# SCH_Potentiometer_Led_MCP3008_2025-04-22.net
KiCad netlist of a schematic drawn in EasyEDA
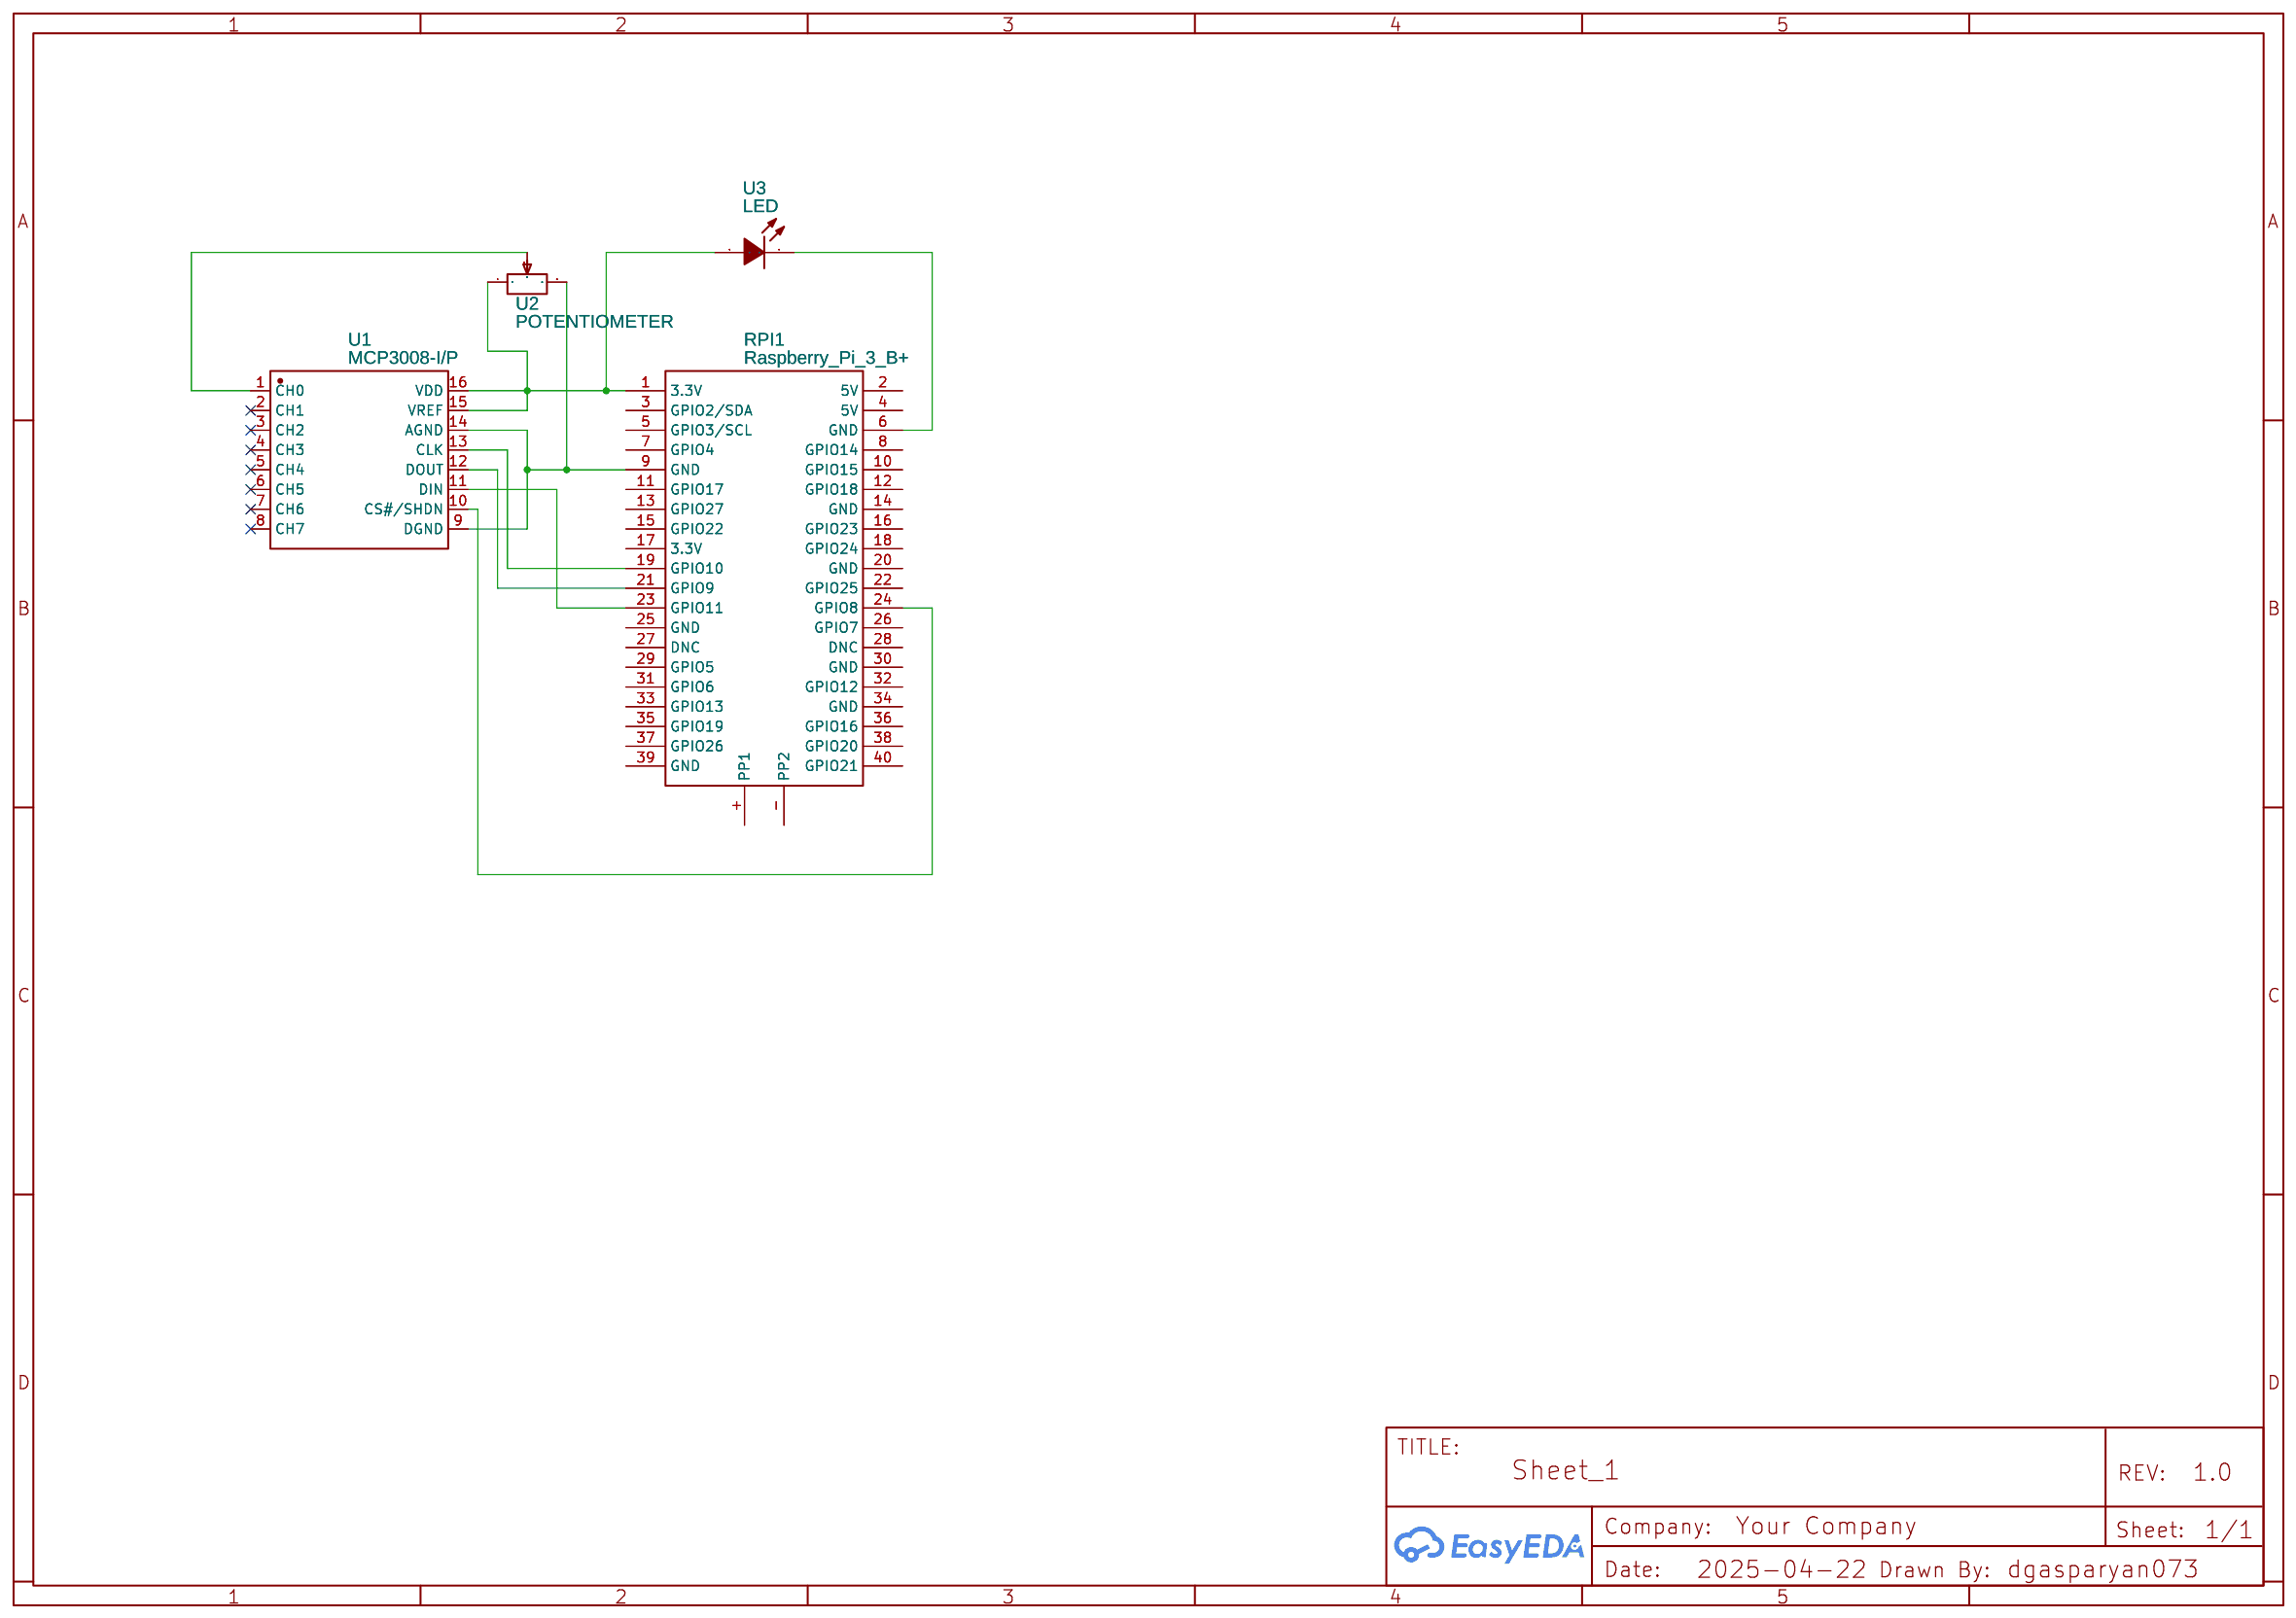
[diagram p0: schematic sheet]

(export (version "E")
  (design (tool "Eeschema 10.0.6"))
  (components
    (comp (ref "RPI1")
      (value "Raspberry_Pi_3_B+")
      (fields
        (field (name "Manufacturer Part") "Raspberry Pi 3 - Model B+ - 1.4GHz Cortex-A53 with 1GB RAM")
        (field (name "Manufacturer") "Raspberry Pi")
      )
      (libsource (lib "") (part "Raspberry_Pi_3_B+"))
    )
    (comp (ref "U1")
      (value "MCP3008-I/P")
      (fields (field (name "Manufacturer") "MICROCHIP(美国微芯)"))
      (libsource (lib "") (part "MCP3008-I/P"))
    )
    (comp (ref "U2")
      (value "POTENTIOMETER")
      (fields (field (name "Manufacturer Part") "3*3Potentiometer-10kΩ20%"))
      (libsource (lib "") (part "3*3POTENTIOMETER-10KΩ20%"))
    )
    (comp (ref "U3")
      (value "LED")
      (fields (field (name "Manufacturer Part") "720-LCGH9RNMXNX1"))
      (libsource (lib "") (part "720-LCGH9RNMXNX1"))
    )
  )
  (nets
    (net (code "1") (name "Net-(RPI1-GPIO8)") (class "Default")
      (node (ref "RPI1") (pin "24") (pinfunction "GPIO8_24") (pintype "bidirectional"))
      (node (ref "U1") (pin "10") (pinfunction "CS#/SHDN_10") (pintype "unspecified"))
    )
    (net (code "2") (name "Net-(RPI1-GPIO9)") (class "Default")
      (node (ref "RPI1") (pin "21") (pinfunction "GPIO9_21") (pintype "bidirectional"))
      (node (ref "U1") (pin "12") (pinfunction "DOUT_12") (pintype "unspecified"))
    )
    (net (code "3") (name "Net-(RPI1-GPIO10)") (class "Default")
      (node (ref "RPI1") (pin "19") (pinfunction "GPIO10_19") (pintype "bidirectional"))
      (node (ref "U1") (pin "13") (pinfunction "CLK_13") (pintype "unspecified"))
    )
    (net (code "4") (name "Net-(RPI1-GPIO11)") (class "Default")
      (node (ref "RPI1") (pin "23") (pinfunction "GPIO11_23") (pintype "bidirectional"))
      (node (ref "U1") (pin "11") (pinfunction "DIN_11") (pintype "unspecified"))
    )
    (net (code "5") (name "Net-(U1-AGND)") (class "Default")
      (node (ref "RPI1") (pin "9") (pinfunction "GND_9") (pintype "unspecified"))
      (node (ref "U1") (pin "14") (pinfunction "AGND_14") (pintype "unspecified"))
      (node (ref "U1") (pin "9") (pinfunction "DGND_9") (pintype "unspecified"))
      (node (ref "U2") (pin "3") (pinfunction "3_3") (pintype "input"))
    )
    (net (code "6") (name "Net-(U1-CH0)") (class "Default")
      (node (ref "U1") (pin "1") (pinfunction "CH0_1") (pintype "unspecified"))
      (node (ref "U2") (pin "2") (pinfunction "2_2") (pintype "input"))
    )
    (net (code "7") (name "Net-(U1-VDD)") (class "Default")
      (node (ref "RPI1") (pin "1") (pinfunction "3.3V_1") (pintype "passive"))
      (node (ref "U1") (pin "15") (pinfunction "VREF_15") (pintype "unspecified"))
      (node (ref "U1") (pin "16") (pinfunction "VDD_16") (pintype "unspecified"))
      (node (ref "U2") (pin "1") (pinfunction "1_1") (pintype "input"))
      (node (ref "U3") (pin "2") (pinfunction "A_2") (pintype "unspecified"))
    )
    (net (code "8") (name "Net-(U3-K)") (class "Default")
      (node (ref "RPI1") (pin "6") (pinfunction "GND_6") (pintype "unspecified"))
      (node (ref "U3") (pin "1") (pinfunction "K_1") (pintype "unspecified"))
    )
    (net (code "9") (name "unconnected-(RPI1-3.3V-Pad17)") (class "Default")
      (node (ref "RPI1") (pin "17") (pinfunction "3.3V_17") (pintype "passive"))
    )
    (net (code "10") (name "unconnected-(RPI1-5V-Pad2)") (class "Default")
      (node (ref "RPI1") (pin "2") (pinfunction "5V_2") (pintype "passive"))
    )
    (net (code "11") (name "unconnected-(RPI1-5V-Pad4)") (class "Default")
      (node (ref "RPI1") (pin "4") (pinfunction "5V_4") (pintype "passive"))
    )
    (net (code "12") (name "unconnected-(RPI1-DNC-Pad27)") (class "Default")
      (node (ref "RPI1") (pin "27") (pinfunction "DNC_27") (pintype "unspecified"))
    )
    (net (code "13") (name "unconnected-(RPI1-DNC-Pad28)") (class "Default")
      (node (ref "RPI1") (pin "28") (pinfunction "DNC_28") (pintype "unspecified"))
    )
    (net (code "14") (name "unconnected-(RPI1-GND-Pad14)") (class "Default")
      (node (ref "RPI1") (pin "14") (pinfunction "GND_14") (pintype "unspecified"))
    )
    (net (code "15") (name "unconnected-(RPI1-GND-Pad20)") (class "Default")
      (node (ref "RPI1") (pin "20") (pinfunction "GND_20") (pintype "unspecified"))
    )
    (net (code "16") (name "unconnected-(RPI1-GND-Pad25)") (class "Default")
      (node (ref "RPI1") (pin "25") (pinfunction "GND_25") (pintype "unspecified"))
    )
    (net (code "17") (name "unconnected-(RPI1-GND-Pad30)") (class "Default")
      (node (ref "RPI1") (pin "30") (pinfunction "GND_30") (pintype "unspecified"))
    )
    (net (code "18") (name "unconnected-(RPI1-GND-Pad34)") (class "Default")
      (node (ref "RPI1") (pin "34") (pinfunction "GND_34") (pintype "unspecified"))
    )
    (net (code "19") (name "unconnected-(RPI1-GND-Pad39)") (class "Default")
      (node (ref "RPI1") (pin "39") (pinfunction "GND_39") (pintype "unspecified"))
    )
    (net (code "20") (name "unconnected-(RPI1-GPIO2{slash}SDA-Pad3)") (class "Default")
      (node (ref "RPI1") (pin "3") (pinfunction "GPIO2/SDA_3") (pintype "bidirectional"))
    )
    (net (code "21") (name "unconnected-(RPI1-GPIO3{slash}SCL-Pad5)") (class "Default")
      (node (ref "RPI1") (pin "5") (pinfunction "GPIO3/SCL_5") (pintype "bidirectional"))
    )
    (net (code "22") (name "unconnected-(RPI1-GPIO4-Pad7)") (class "Default")
      (node (ref "RPI1") (pin "7") (pinfunction "GPIO4_7") (pintype "bidirectional"))
    )
    (net (code "23") (name "unconnected-(RPI1-GPIO5-Pad29)") (class "Default")
      (node (ref "RPI1") (pin "29") (pinfunction "GPIO5_29") (pintype "bidirectional"))
    )
    (net (code "24") (name "unconnected-(RPI1-GPIO6-Pad31)") (class "Default")
      (node (ref "RPI1") (pin "31") (pinfunction "GPIO6_31") (pintype "bidirectional"))
    )
    (net (code "25") (name "unconnected-(RPI1-GPIO7-Pad26)") (class "Default")
      (node (ref "RPI1") (pin "26") (pinfunction "GPIO7_26") (pintype "bidirectional"))
    )
    (net (code "26") (name "unconnected-(RPI1-GPIO12-Pad32)") (class "Default")
      (node (ref "RPI1") (pin "32") (pinfunction "GPIO12_32") (pintype "bidirectional"))
    )
    (net (code "27") (name "unconnected-(RPI1-GPIO13-Pad33)") (class "Default")
      (node (ref "RPI1") (pin "33") (pinfunction "GPIO13_33") (pintype "bidirectional"))
    )
    (net (code "28") (name "unconnected-(RPI1-GPIO14-Pad8)") (class "Default")
      (node (ref "RPI1") (pin "8") (pinfunction "GPIO14_8") (pintype "bidirectional"))
    )
    (net (code "29") (name "unconnected-(RPI1-GPIO15-Pad10)") (class "Default")
      (node (ref "RPI1") (pin "10") (pinfunction "GPIO15_10") (pintype "bidirectional"))
    )
    (net (code "30") (name "unconnected-(RPI1-GPIO16-Pad36)") (class "Default")
      (node (ref "RPI1") (pin "36") (pinfunction "GPIO16_36") (pintype "bidirectional"))
    )
    (net (code "31") (name "unconnected-(RPI1-GPIO17-Pad11)") (class "Default")
      (node (ref "RPI1") (pin "11") (pinfunction "GPIO17_11") (pintype "bidirectional"))
    )
    (net (code "32") (name "unconnected-(RPI1-GPIO18-Pad12)") (class "Default")
      (node (ref "RPI1") (pin "12") (pinfunction "GPIO18_12") (pintype "bidirectional"))
    )
    (net (code "33") (name "unconnected-(RPI1-GPIO19-Pad35)") (class "Default")
      (node (ref "RPI1") (pin "35") (pinfunction "GPIO19_35") (pintype "bidirectional"))
    )
    (net (code "34") (name "unconnected-(RPI1-GPIO20-Pad38)") (class "Default")
      (node (ref "RPI1") (pin "38") (pinfunction "GPIO20_38") (pintype "bidirectional"))
    )
    (net (code "35") (name "unconnected-(RPI1-GPIO21-Pad40)") (class "Default")
      (node (ref "RPI1") (pin "40") (pinfunction "GPIO21_40") (pintype "bidirectional"))
    )
    (net (code "36") (name "unconnected-(RPI1-GPIO22-Pad15)") (class "Default")
      (node (ref "RPI1") (pin "15") (pinfunction "GPIO22_15") (pintype "bidirectional"))
    )
    (net (code "37") (name "unconnected-(RPI1-GPIO23-Pad16)") (class "Default")
      (node (ref "RPI1") (pin "16") (pinfunction "GPIO23_16") (pintype "bidirectional"))
    )
    (net (code "38") (name "unconnected-(RPI1-GPIO24-Pad18)") (class "Default")
      (node (ref "RPI1") (pin "18") (pinfunction "GPIO24_18") (pintype "bidirectional"))
    )
    (net (code "39") (name "unconnected-(RPI1-GPIO25-Pad22)") (class "Default")
      (node (ref "RPI1") (pin "22") (pinfunction "GPIO25_22") (pintype "bidirectional"))
    )
    (net (code "40") (name "unconnected-(RPI1-GPIO26-Pad37)") (class "Default")
      (node (ref "RPI1") (pin "37") (pinfunction "GPIO26_37") (pintype "bidirectional"))
    )
    (net (code "41") (name "unconnected-(RPI1-GPIO27-Pad13)") (class "Default")
      (node (ref "RPI1") (pin "13") (pinfunction "GPIO27_13") (pintype "bidirectional"))
    )
    (net (code "42") (name "unconnected-(RPI1-PP1-Pad+)") (class "Default")
      (node (ref "RPI1") (pin "+") (pinfunction "PP1_+") (pintype "unspecified"))
    )
    (net (code "43") (name "unconnected-(RPI1-PP2-Pad-)") (class "Default")
      (node (ref "RPI1") (pin "-") (pinfunction "PP2_-") (pintype "unspecified"))
    )
    (net (code "44") (name "unconnected-(U1-CH1-Pad2)") (class "Default")
      (node (ref "U1") (pin "2") (pinfunction "CH1_2") (pintype "unspecified+no_connect"))
    )
    (net (code "45") (name "unconnected-(U1-CH2-Pad3)") (class "Default")
      (node (ref "U1") (pin "3") (pinfunction "CH2_3") (pintype "unspecified+no_connect"))
    )
    (net (code "46") (name "unconnected-(U1-CH3-Pad4)") (class "Default")
      (node (ref "U1") (pin "4") (pinfunction "CH3_4") (pintype "unspecified+no_connect"))
    )
    (net (code "47") (name "unconnected-(U1-CH4-Pad5)") (class "Default")
      (node (ref "U1") (pin "5") (pinfunction "CH4_5") (pintype "unspecified+no_connect"))
    )
    (net (code "48") (name "unconnected-(U1-CH5-Pad6)") (class "Default")
      (node (ref "U1") (pin "6") (pinfunction "CH5_6") (pintype "unspecified+no_connect"))
    )
    (net (code "49") (name "unconnected-(U1-CH6-Pad7)") (class "Default")
      (node (ref "U1") (pin "7") (pinfunction "CH6_7") (pintype "unspecified+no_connect"))
    )
    (net (code "50") (name "unconnected-(U1-CH7-Pad8)") (class "Default")
      (node (ref "U1") (pin "8") (pinfunction "CH7_8") (pintype "unspecified+no_connect"))
    )
  )
)
